# motherboard_rev1.net
KiCad netlist of a schematic drawn in EAGLE
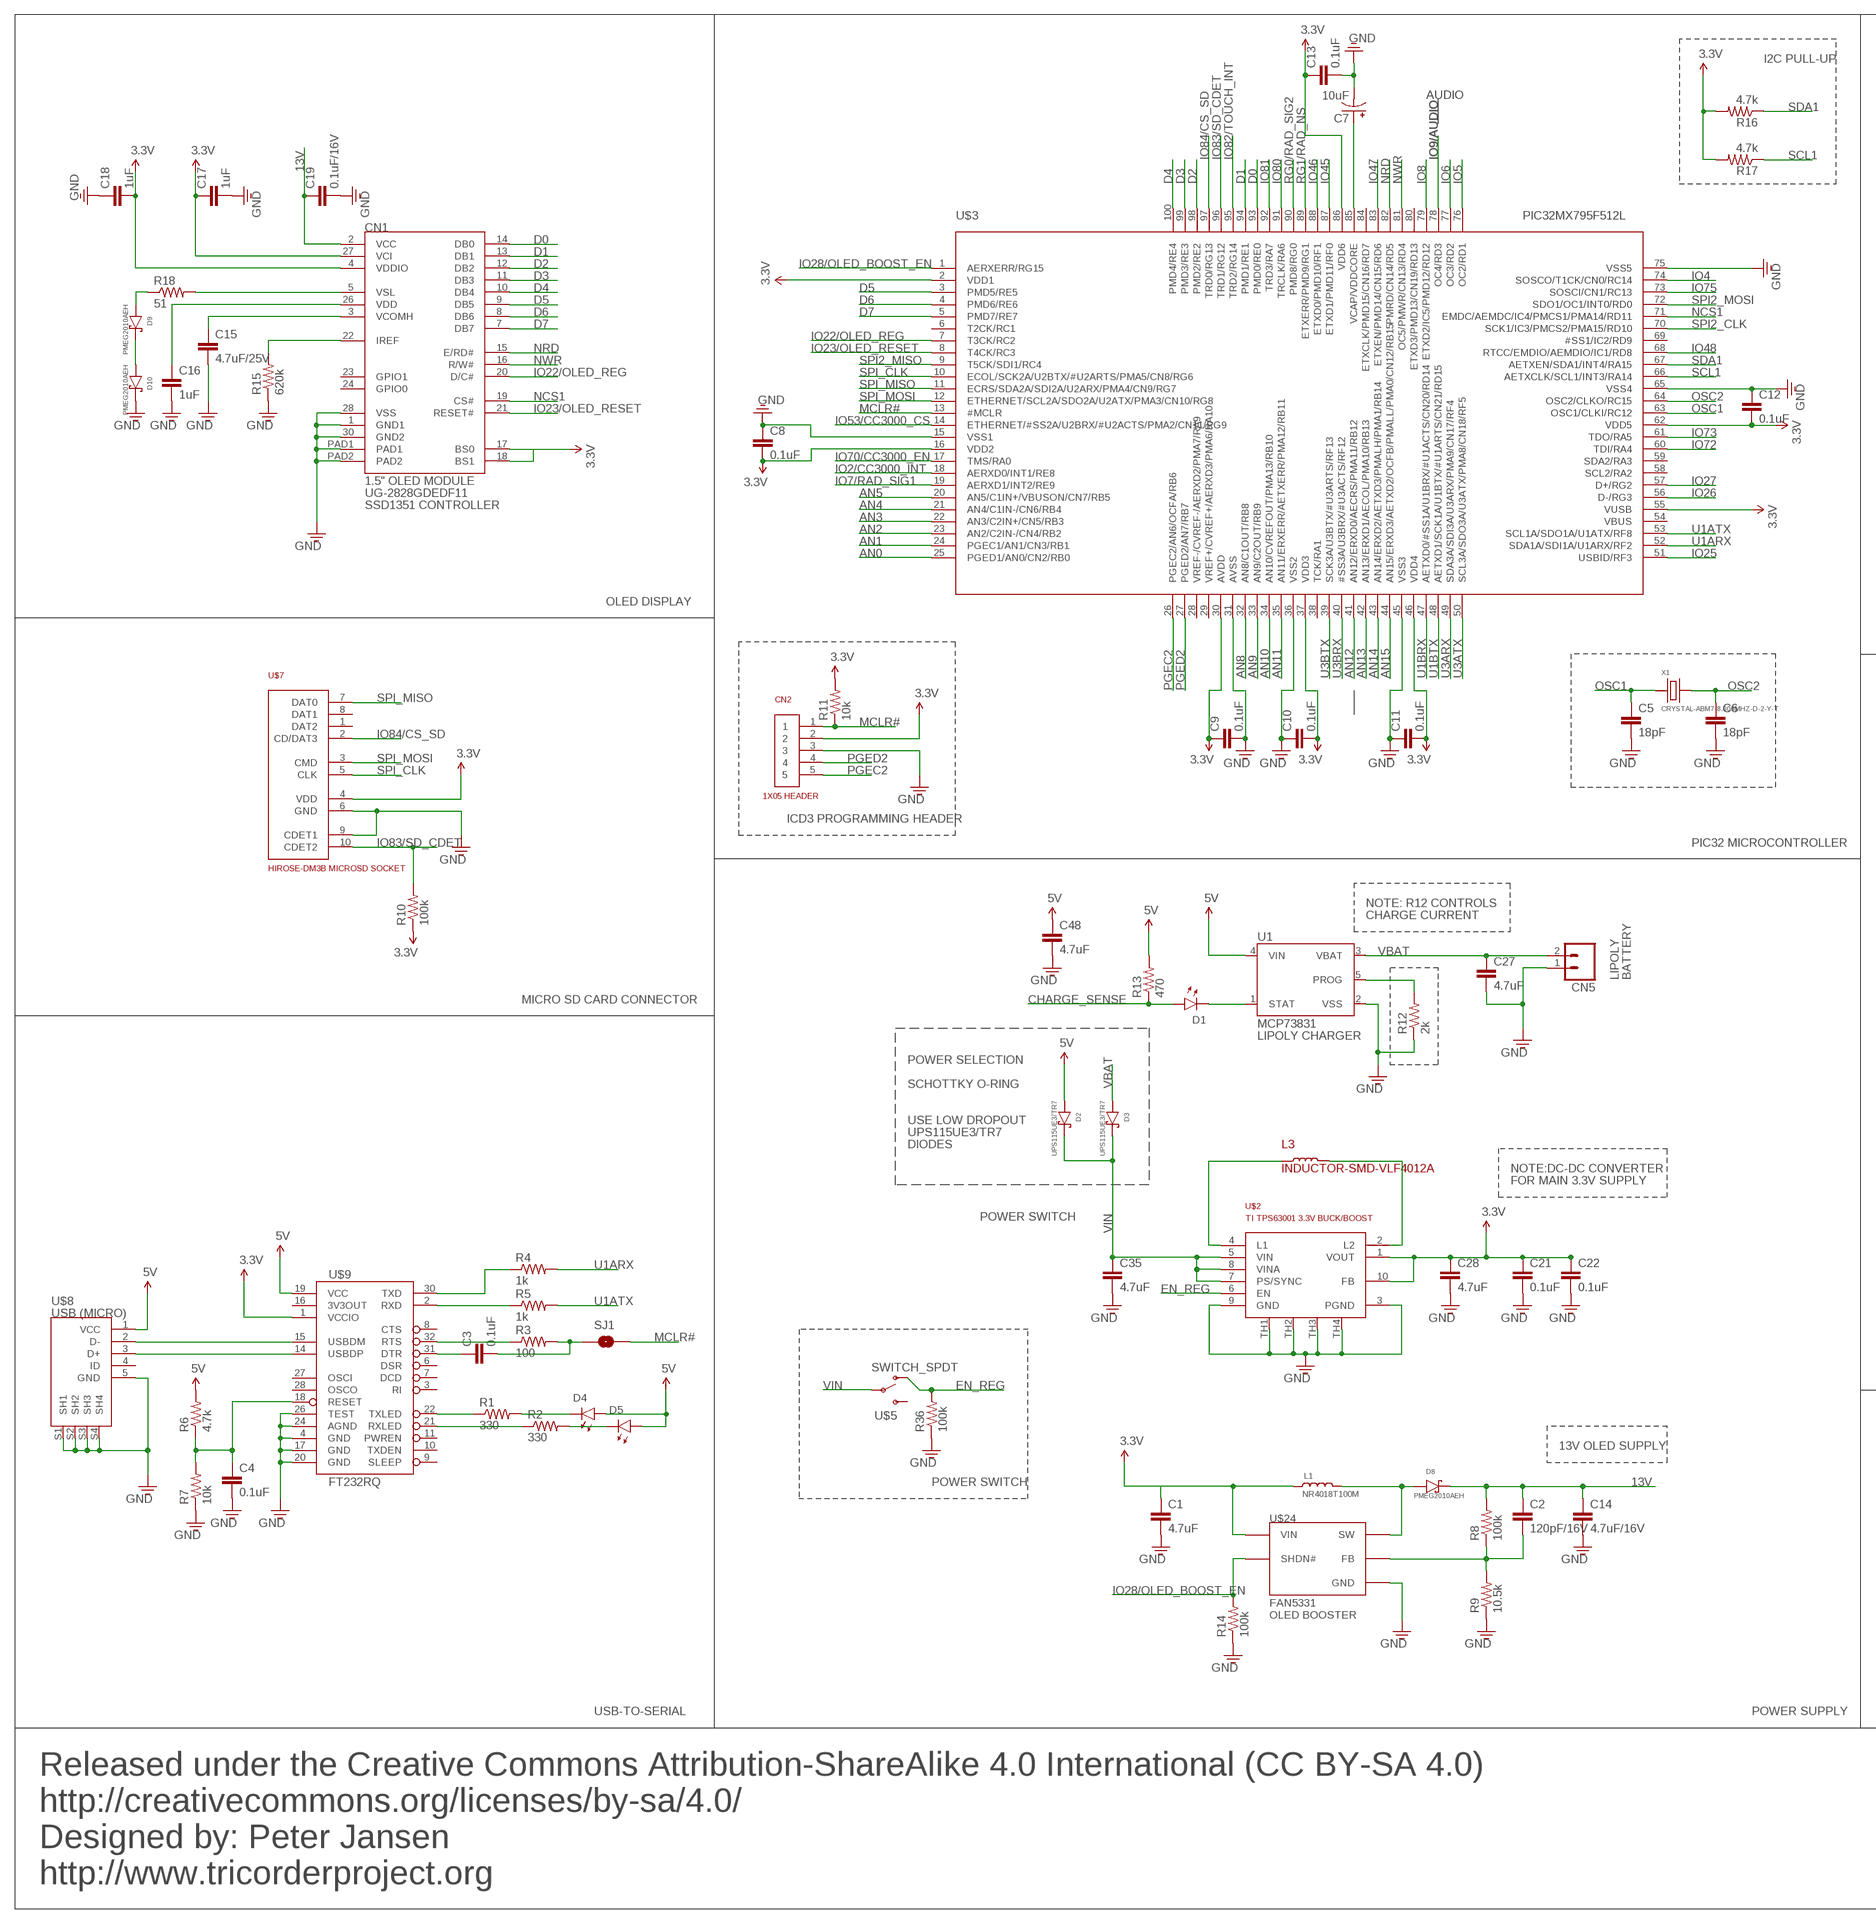
[diagram p0: schematic, sheet 1, part 1 of 2]
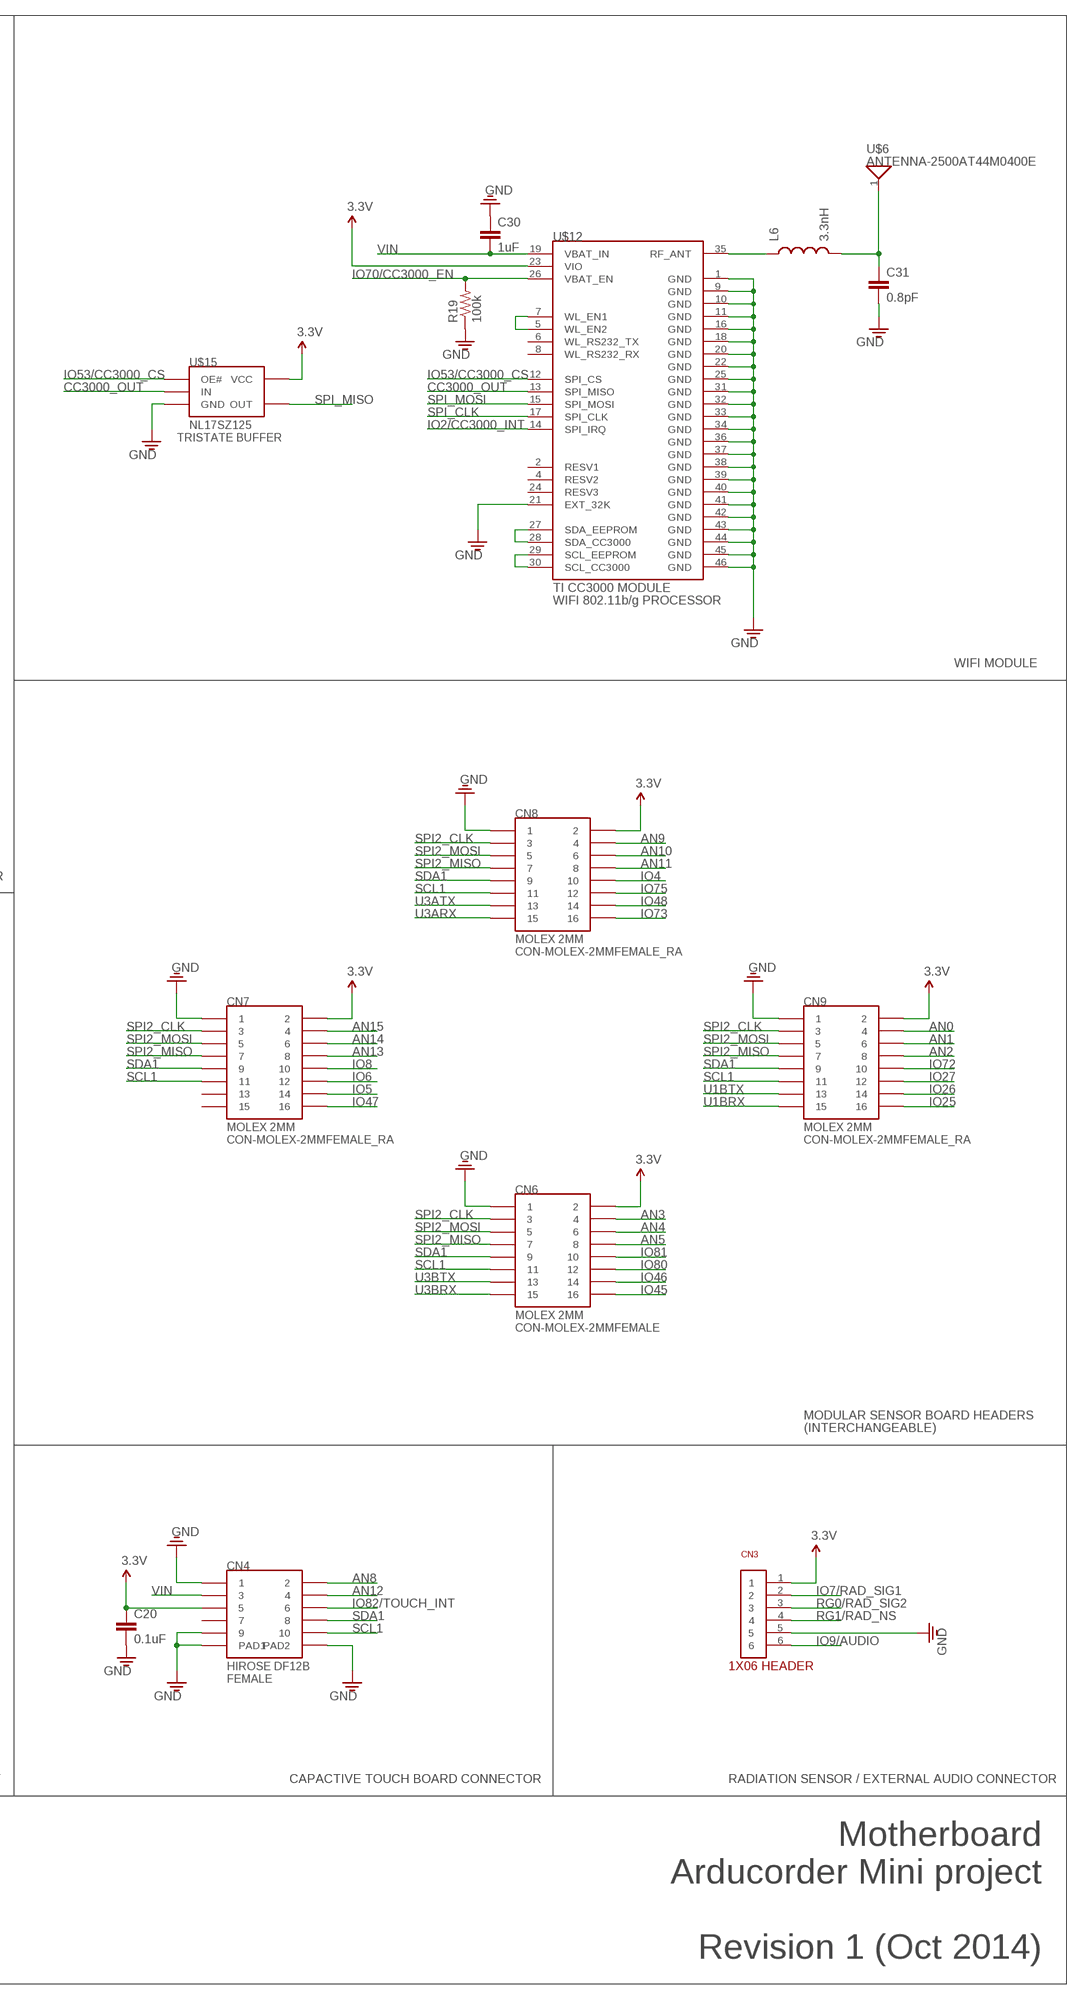
[diagram p1: schematic, sheet 1, part 2 of 2]

(export (version "E")
  (design (tool "Eeschema 10.0.6"))
  (components
    (comp (ref "C1")
      (value "4.7uF")
      (footprint "eagle-import:0603")
      (libsource (lib "eagle-import") (part "CAP0603"))
    )
    (comp (ref "C2")
      (value "120pF/16V")
      (footprint "eagle-import:0603")
      (libsource (lib "eagle-import") (part "notes_mark5a1_CAP0603"))
    )
    (comp (ref "C3")
      (value "0.1uF")
      (footprint "eagle-import:0603")
      (libsource (lib "eagle-import") (part "CAP0603"))
    )
    (comp (ref "C4")
      (value "0.1uF")
      (footprint "eagle-import:0603")
      (libsource (lib "eagle-import") (part "CAP0603"))
    )
    (comp (ref "C5")
      (value "18pF")
      (footprint "eagle-import:0603")
      (libsource (lib "eagle-import") (part "CAP0603"))
    )
    (comp (ref "C6")
      (value "18pF")
      (footprint "eagle-import:0603")
      (libsource (lib "eagle-import") (part "CAP0603"))
    )
    (comp (ref "C7")
      (value "10uF")
      (footprint "eagle-import:EIA3216")
      (libsource (lib "eagle-import") (part "CAP_POL1206"))
    )
    (comp (ref "C8")
      (value "0.1uF")
      (footprint "eagle-import:0603")
      (libsource (lib "eagle-import") (part "CAP0603"))
    )
    (comp (ref "C9")
      (value "0.1uF")
      (footprint "eagle-import:0603")
      (libsource (lib "eagle-import") (part "CAP0603"))
    )
    (comp (ref "C10")
      (value "0.1uF")
      (footprint "eagle-import:0603")
      (libsource (lib "eagle-import") (part "CAP0603"))
    )
    (comp (ref "C11")
      (value "0.1uF")
      (footprint "eagle-import:0603")
      (libsource (lib "eagle-import") (part "CAP0603"))
    )
    (comp (ref "C12")
      (value "0.1uF")
      (footprint "eagle-import:0603")
      (libsource (lib "eagle-import") (part "CAP0603"))
    )
    (comp (ref "C13")
      (value "0.1uF")
      (footprint "eagle-import:0603")
      (libsource (lib "eagle-import") (part "CAP0603"))
    )
    (comp (ref "C14")
      (value "4.7uF/16V")
      (footprint "eagle-import:0603")
      (libsource (lib "eagle-import") (part "CAP0603"))
    )
    (comp (ref "C15")
      (value "4.7uF/25V")
      (footprint "eagle-import:0603")
      (libsource (lib "eagle-import") (part "CAP0603"))
    )
    (comp (ref "C16")
      (value "1uF")
      (footprint "eagle-import:0603")
      (libsource (lib "eagle-import") (part "CAP0603"))
    )
    (comp (ref "C17")
      (value "1uF")
      (footprint "eagle-import:0603")
      (libsource (lib "eagle-import") (part "CAP0603"))
    )
    (comp (ref "C18")
      (value "1uF")
      (footprint "eagle-import:0603")
      (libsource (lib "eagle-import") (part "CAP0603"))
    )
    (comp (ref "C19")
      (value "0.1uF/16V")
      (footprint "eagle-import:0603")
      (libsource (lib "eagle-import") (part "CAP0603"))
    )
    (comp (ref "C20")
      (value "0.1uF")
      (footprint "eagle-import:0603")
      (libsource (lib "eagle-import") (part "CAP0603"))
    )
    (comp (ref "C21")
      (value "0.1uF")
      (footprint "eagle-import:0603")
      (libsource (lib "eagle-import") (part "CAP0603"))
    )
    (comp (ref "C22")
      (value "0.1uF")
      (footprint "eagle-import:0603")
      (libsource (lib "eagle-import") (part "CAP0603"))
    )
    (comp (ref "C27")
      (value "4.7uF")
      (footprint "eagle-import:0603")
      (libsource (lib "eagle-import") (part "CAP0603"))
    )
    (comp (ref "C28")
      (value "4.7uF")
      (footprint "eagle-import:0603")
      (libsource (lib "eagle-import") (part "CAP0603"))
    )
    (comp (ref "C30")
      (value "1uF")
      (footprint "eagle-import:0603")
      (libsource (lib "eagle-import") (part "CAP0603"))
    )
    (comp (ref "C31")
      (value "0.8pF")
      (footprint "eagle-import:C0402")
      (libsource (lib "eagle-import") (part "CAP0402"))
    )
    (comp (ref "C35")
      (value "4.7uF")
      (footprint "eagle-import:0603")
      (libsource (lib "eagle-import") (part "CAP0603"))
    )
    (comp (ref "C48")
      (value "4.7uF")
      (footprint "eagle-import:0603")
      (libsource (lib "eagle-import") (part "CAP0603"))
    )
    (comp (ref "CN1")
      (value "UG-2828GDEDF11-1.5OLED")
      (footprint "eagle-import:XF2M-3015-1A-1.5LCD")
      (libsource (lib "eagle-import") (part "UG-2828GDEDF11-1.5OLED"))
    )
    (comp (ref "CN2")
      (value "1X05")
      (footprint "eagle-import:1X05")
      (libsource (lib "eagle-import") (part "1X05"))
    )
    (comp (ref "CN3")
      (value "PHF-106-01-L-S")
      (footprint "eagle-import:1X06")
      (libsource (lib "eagle-import") (part "1X06"))
    )
    (comp (ref "CN4")
      (value "FEMALE")
      (footprint "eagle-import:DF12B(3.0)-10DP-0.5V(86)")
      (libsource (lib "eagle-import") (part "CON-HIROSE-DF12FEMALE"))
    )
    (comp (ref "CN5")
      (value "M02-JST-2MM-SMT")
      (footprint "eagle-import:JST-2-SMD")
      (libsource (lib "eagle-import") (part "M02-JST-2MM-SMT"))
    )
    (comp (ref "CN6")
      (value "CON-MOLEX-2MMFEMALE")
      (footprint "eagle-import:MOLEX-0791091007")
      (libsource (lib "eagle-import") (part "CON-MOLEX-2MMFEMALE"))
    )
    (comp (ref "CN7")
      (value "CON-MOLEX-2MMFEMALE_RA")
      (footprint "eagle-import:MOLEX-87368-1624")
      (libsource (lib "eagle-import") (part "CON-MOLEX-2MMFEMALE_RA"))
    )
    (comp (ref "CN8")
      (value "CON-MOLEX-2MMFEMALE_RA")
      (footprint "eagle-import:MOLEX-87368-1624")
      (libsource (lib "eagle-import") (part "CON-MOLEX-2MMFEMALE_RA"))
    )
    (comp (ref "CN9")
      (value "CON-MOLEX-2MMFEMALE_RA")
      (footprint "eagle-import:MOLEX-87368-1624")
      (libsource (lib "eagle-import") (part "CON-MOLEX-2MMFEMALE_RA"))
    )
    (comp (ref "D1")
      (value "0605-LED")
      (footprint "eagle-import:0603-LED")
      (libsource (lib "eagle-import") (part "0605-LED"))
    )
    (comp (ref "D2")
      (value "UPS115UE3/TR7")
      (footprint "eagle-import:DO-214BA")
      (libsource (lib "eagle-import") (part "DIODE-SCHOTTKY"))
    )
    (comp (ref "D3")
      (value "UPS115UE3/TR7")
      (footprint "eagle-import:DO-214BA")
      (libsource (lib "eagle-import") (part "DIODE-SCHOTTKY"))
    )
    (comp (ref "D4")
      (value "0605-LED")
      (footprint "eagle-import:0603-LED")
      (libsource (lib "eagle-import") (part "0605-LED"))
    )
    (comp (ref "D5")
      (value "0605-LED")
      (footprint "eagle-import:0603-LED")
      (libsource (lib "eagle-import") (part "0605-LED"))
    )
    (comp (ref "D8")
      (value "PMEG2010AEH")
      (footprint "eagle-import:SOD123F")
      (libsource (lib "eagle-import") (part "DIODE-SCHOTTKYSOD123F"))
    )
    (comp (ref "D9")
      (value "PMEG2010AEH")
      (footprint "eagle-import:SOD123F")
      (libsource (lib "eagle-import") (part "DIODE-SCHOTTKYSOD123F"))
    )
    (comp (ref "D10")
      (value "PMEG2010AEH")
      (footprint "eagle-import:SOD123F")
      (libsource (lib "eagle-import") (part "DIODE-SCHOTTKYSOD123F"))
    )
    (comp (ref "L1")
      (value "NR4018T100M")
      (footprint "eagle-import:NR4018T100M")
      (libsource (lib "eagle-import") (part "INDUCTORNR4018T100M"))
    )
    (comp (ref "L3")
      (value "INDUCTOR-SMD-VLF4012A")
      (footprint "eagle-import:VLF4012A")
      (libsource (lib "eagle-import") (part "INDUCTOR-SMD-VLF4012A"))
    )
    (comp (ref "L6")
      (value "3.3nH")
      (footprint "eagle-import:C0402")
      (libsource (lib "eagle-import") (part "INDUCTOR0402"))
    )
    (comp (ref "R1")
      (value "330")
      (footprint "eagle-import:0603")
      (libsource (lib "eagle-import") (part "RESISTOR0603"))
    )
    (comp (ref "R2")
      (value "330")
      (footprint "eagle-import:0603")
      (libsource (lib "eagle-import") (part "RESISTOR0603"))
    )
    (comp (ref "R3")
      (value "100")
      (footprint "eagle-import:0603")
      (libsource (lib "eagle-import") (part "RESISTOR0603"))
    )
    (comp (ref "R4")
      (value "1k")
      (footprint "eagle-import:0603")
      (libsource (lib "eagle-import") (part "RESISTOR0603"))
    )
    (comp (ref "R5")
      (value "1k")
      (footprint "eagle-import:0603")
      (libsource (lib "eagle-import") (part "RESISTOR0603"))
    )
    (comp (ref "R6")
      (value "4.7k")
      (footprint "eagle-import:0603")
      (libsource (lib "eagle-import") (part "RESISTOR0603"))
    )
    (comp (ref "R7")
      (value "10k")
      (footprint "eagle-import:0603")
      (libsource (lib "eagle-import") (part "RESISTOR0603"))
    )
    (comp (ref "R8")
      (value "100k")
      (footprint "eagle-import:0603")
      (libsource (lib "eagle-import") (part "notes_mark5a1_RESISTOR0603"))
    )
    (comp (ref "R9")
      (value "10.5k")
      (footprint "eagle-import:0603")
      (libsource (lib "eagle-import") (part "notes_mark5a1_RESISTOR0603"))
    )
    (comp (ref "R10")
      (value "100k")
      (footprint "eagle-import:0603")
      (libsource (lib "eagle-import") (part "RESISTOR0603"))
    )
    (comp (ref "R11")
      (value "10k")
      (footprint "eagle-import:0603")
      (libsource (lib "eagle-import") (part "RESISTOR0603"))
    )
    (comp (ref "R12")
      (value "2k")
      (footprint "eagle-import:0603")
      (libsource (lib "eagle-import") (part "RESISTOR0603"))
    )
    (comp (ref "R13")
      (value "470")
      (footprint "eagle-import:0603")
      (libsource (lib "eagle-import") (part "RESISTOR0603"))
    )
    (comp (ref "R14")
      (value "100k")
      (footprint "eagle-import:0603")
      (libsource (lib "eagle-import") (part "notes_mark5a1_RESISTOR0603"))
    )
    (comp (ref "R15")
      (value "620k")
      (footprint "eagle-import:0603")
      (libsource (lib "eagle-import") (part "notes_mark5a1_RESISTOR0603"))
    )
    (comp (ref "R16")
      (value "4.7k")
      (footprint "eagle-import:0603")
      (libsource (lib "eagle-import") (part "RESISTOR0603"))
    )
    (comp (ref "R17")
      (value "4.7k")
      (footprint "eagle-import:0603")
      (libsource (lib "eagle-import") (part "RESISTOR0603"))
    )
    (comp (ref "R18")
      (value "51")
      (footprint "eagle-import:0603")
      (libsource (lib "eagle-import") (part "notes_mark5a1_RESISTOR0603"))
    )
    (comp (ref "R19")
      (value "100k")
      (footprint "eagle-import:0603")
      (libsource (lib "eagle-import") (part "notes_mark5a1_RESISTOR0603"))
    )
    (comp (ref "R36")
      (value "100k")
      (footprint "eagle-import:0603")
      (libsource (lib "eagle-import") (part "RESISTOR0603"))
    )
    (comp (ref "SJ1")
      (value "SOLDERJUMPERTRACE")
      (footprint "eagle-import:SJ_2S-TRACE")
      (libsource (lib "eagle-import") (part "SOLDERJUMPERTRACE"))
    )
    (comp (ref "U$2")
      (value "TI-TPS63001-3.3V-BUCKBOOST")
      (footprint "eagle-import:TPS63001")
      (libsource (lib "eagle-import") (part "TI-TPS63001-3.3V-BUCKBOOST"))
    )
    (comp (ref "U$3")
      (value "PIC32MX795F512L-80I/PF")
      (footprint "eagle-import:SQFP-S-14X14-100")
      (libsource (lib "eagle-import") (part "PIC32MX795F512L-80I/PF"))
    )
    (comp (ref "U$5")
      (value "SWITCH_SPDT")
      (footprint "eagle-import:KPS-1290")
      (libsource (lib "eagle-import") (part "SWITCH_SPDT"))
    )
    (comp (ref "U$6")
      (value "ANTENNA-2500AT44M0400E")
      (footprint "eagle-import:ANT-2500AT44M0400E")
      (libsource (lib "eagle-import") (part "ANTENNA-2500AT44M0400E"))
    )
    (comp (ref "U$7")
      (value "CON-HIROSE-DM3B-MICROSD")
      (footprint "eagle-import:CON-HIROSE-DM3B-MICROSD")
      (libsource (lib "eagle-import") (part "CON-HIROSE-DM3B-MICROSD"))
    )
    (comp (ref "U$8")
      (value "USB-MICROB")
      (footprint "eagle-import:FCI-10104110-0001LF")
      (libsource (lib "eagle-import") (part "USB-MICROB"))
    )
    (comp (ref "U$9")
      (value "FT232RQ")
      (footprint "eagle-import:QFN-32")
      (libsource (lib "eagle-import") (part "FT232RQ"))
    )
    (comp (ref "U$12")
      (value "CC3000")
      (footprint "eagle-import:CC3000")
      (libsource (lib "eagle-import") (part "CC3000"))
    )
    (comp (ref "U$15")
      (value "BUFFER-NL17SZ125")
      (footprint "eagle-import:TSOP-5")
      (libsource (lib "eagle-import") (part "BUFFER-NL17SZ125"))
    )
    (comp (ref "U$24")
      (value "FAN5331-BOOST")
      (footprint "eagle-import:TSOP-5")
      (libsource (lib "eagle-import") (part "FAN5331-BOOST"))
    )
    (comp (ref "U1")
      (value "MCP73831")
      (footprint "eagle-import:SOT23-5")
      (libsource (lib "eagle-import") (part "MCP73831"))
    )
    (comp (ref "X1")
      (value "CRYSTAL-ABM7-8.000MHZ-D-2-Y-T")
      (footprint "eagle-import:CYRSTAL-6.0X3.5MM")
      (libsource (lib "eagle-import") (part "CRYSTAL-ABM7-8.000MHZ-D-2-Y-T"))
    )
  )
  (nets
    (net (code "1") (name "/13V") (class "Default")
      (node (ref "C14") (pin "1") (pinfunction "1_1") (pintype "passive"))
      (node (ref "C19") (pin "1") (pinfunction "1_1") (pintype "passive"))
      (node (ref "C2") (pin "1") (pinfunction "1_1") (pintype "passive"))
      (node (ref "CN1") (pin "2") (pinfunction "VCC_2") (pintype "bidirectional"))
      (node (ref "D8") (pin "1") (pinfunction "CATHODE_1") (pintype "bidirectional"))
      (node (ref "R8") (pin "2") (pinfunction "2_2") (pintype "passive"))
    )
    (net (code "2") (name "/AN0") (class "Default")
      (node (ref "CN9") (pin "4") (pinfunction "4_4") (pintype "bidirectional"))
      (node (ref "U$3") (pin "25") (pinfunction "PGED1/AN0/CN2/RB0_25") (pintype "bidirectional"))
    )
    (net (code "3") (name "/AN1") (class "Default")
      (node (ref "CN9") (pin "6") (pinfunction "6_6") (pintype "bidirectional"))
      (node (ref "U$3") (pin "24") (pinfunction "PGEC1/AN1/CN3/RB1_24") (pintype "bidirectional"))
    )
    (net (code "4") (name "/AN2") (class "Default")
      (node (ref "CN9") (pin "8") (pinfunction "8_8") (pintype "bidirectional"))
      (node (ref "U$3") (pin "23") (pinfunction "AN2/C2IN-/CN4/RB2_23") (pintype "bidirectional"))
    )
    (net (code "5") (name "/AN3") (class "Default")
      (node (ref "CN6") (pin "4") (pinfunction "4_4") (pintype "bidirectional"))
      (node (ref "U$3") (pin "22") (pinfunction "AN3/C2IN+/CN5/RB3_22") (pintype "bidirectional"))
    )
    (net (code "6") (name "/AN4") (class "Default")
      (node (ref "CN6") (pin "6") (pinfunction "6_6") (pintype "bidirectional"))
      (node (ref "U$3") (pin "21") (pinfunction "AN4/C1IN-/CN6/RB4_21") (pintype "bidirectional"))
    )
    (net (code "7") (name "/AN5") (class "Default")
      (node (ref "CN6") (pin "8") (pinfunction "8_8") (pintype "bidirectional"))
      (node (ref "U$3") (pin "20") (pinfunction "AN5/C1IN+/VBUSON/CN7/RB5_20") (pintype "bidirectional"))
    )
    (net (code "8") (name "/AN8") (class "Default")
      (node (ref "CN4") (pin "2") (pinfunction "2_2") (pintype "bidirectional"))
      (node (ref "U$3") (pin "32") (pinfunction "AN8/C1OUT/RB8_32") (pintype "bidirectional"))
    )
    (net (code "9") (name "/AN9") (class "Default")
      (node (ref "CN8") (pin "4") (pinfunction "4_4") (pintype "bidirectional"))
      (node (ref "U$3") (pin "33") (pinfunction "AN9/C2OUT/RB9_33") (pintype "bidirectional"))
    )
    (net (code "10") (name "/AN10") (class "Default")
      (node (ref "CN8") (pin "6") (pinfunction "6_6") (pintype "bidirectional"))
      (node (ref "U$3") (pin "34") (pinfunction "AN10/CVREFOUT/PMA13/RB10_34") (pintype "bidirectional"))
    )
    (net (code "11") (name "/AN11") (class "Default")
      (node (ref "CN8") (pin "8") (pinfunction "8_8") (pintype "bidirectional"))
      (node (ref "U$3") (pin "35") (pinfunction "AN11/ERXERR/AETXERR/PMA12/RB11_35") (pintype "bidirectional"))
    )
    (net (code "12") (name "/AN12") (class "Default")
      (node (ref "CN4") (pin "4") (pinfunction "4_4") (pintype "bidirectional"))
      (node (ref "U$3") (pin "41") (pinfunction "AN12/ERXD0/AECRS/PMA11/RB12_41") (pintype "bidirectional"))
    )
    (net (code "13") (name "/AN13") (class "Default")
      (node (ref "CN7") (pin "8") (pinfunction "8_8") (pintype "bidirectional"))
      (node (ref "U$3") (pin "42") (pinfunction "AN13/ERXD1/AECOL/PMA10/RB13_42") (pintype "bidirectional"))
    )
    (net (code "14") (name "/AN14") (class "Default")
      (node (ref "CN7") (pin "6") (pinfunction "6_6") (pintype "bidirectional"))
      (node (ref "U$3") (pin "43") (pinfunction "AN14/ERXD2/AETXD3/PMALH/PMA1/RB14_43") (pintype "bidirectional"))
    )
    (net (code "15") (name "/AN15") (class "Default")
      (node (ref "CN7") (pin "4") (pinfunction "4_4") (pintype "bidirectional"))
      (node (ref "U$3") (pin "44") (pinfunction "AN15/ERXD3/AETXD2/OCFB/PMALL/PMA0/CN12/RB15_44") (pintype "bidirectional"))
    )
    (net (code "16") (name "/CC3000_OUT") (class "Default")
      (node (ref "U$12") (pin "13") (pinfunction "SPI_MISO_13") (pintype "bidirectional"))
      (node (ref "U$15") (pin "2") (pinfunction "IN_2") (pintype "bidirectional"))
    )
    (net (code "17") (name "/CHARGE_SENSE") (class "Default")
      (node (ref "D1") (pin "ANODE") (pinfunction "ANODE_ANODE") (pintype "bidirectional"))
      (node (ref "R13") (pin "1") (pinfunction "1_1") (pintype "passive"))
    )
    (net (code "18") (name "/D0") (class "Default")
      (node (ref "CN1") (pin "14") (pinfunction "DB0_14") (pintype "bidirectional"))
      (node (ref "U$3") (pin "93") (pinfunction "PMD0/RE0_93") (pintype "bidirectional"))
    )
    (net (code "19") (name "/D1") (class "Default")
      (node (ref "CN1") (pin "13") (pinfunction "DB1_13") (pintype "bidirectional"))
      (node (ref "U$3") (pin "94") (pinfunction "PMD1/RE1_94") (pintype "bidirectional"))
    )
    (net (code "20") (name "/D2") (class "Default")
      (node (ref "CN1") (pin "12") (pinfunction "DB2_12") (pintype "bidirectional"))
      (node (ref "U$3") (pin "98") (pinfunction "PMD2/RE2_98") (pintype "bidirectional"))
    )
    (net (code "21") (name "/D3") (class "Default")
      (node (ref "CN1") (pin "11") (pinfunction "DB3_11") (pintype "bidirectional"))
      (node (ref "U$3") (pin "99") (pinfunction "PMD3/RE3_99") (pintype "bidirectional"))
    )
    (net (code "22") (name "/D4") (class "Default")
      (node (ref "CN1") (pin "10") (pinfunction "DB4_10") (pintype "bidirectional"))
      (node (ref "U$3") (pin "100") (pinfunction "PMD4/RE4_100") (pintype "bidirectional"))
    )
    (net (code "23") (name "/D5") (class "Default")
      (node (ref "CN1") (pin "9") (pinfunction "DB5_9") (pintype "bidirectional"))
      (node (ref "U$3") (pin "3") (pinfunction "PMD5/RE5_3") (pintype "bidirectional"))
    )
    (net (code "24") (name "/D6") (class "Default")
      (node (ref "CN1") (pin "8") (pinfunction "DB6_8") (pintype "bidirectional"))
      (node (ref "U$3") (pin "4") (pinfunction "PMD6/RE6_4") (pintype "bidirectional"))
    )
    (net (code "25") (name "/D7") (class "Default")
      (node (ref "CN1") (pin "7") (pinfunction "DB7_7") (pintype "bidirectional"))
      (node (ref "U$3") (pin "5") (pinfunction "PMD7/RE7_5") (pintype "bidirectional"))
    )
    (net (code "26") (name "/EN_REG") (class "Default")
      (node (ref "R36") (pin "2") (pinfunction "2_2") (pintype "passive"))
      (node (ref "U$2") (pin "6") (pinfunction "EN_6") (pintype "bidirectional"))
      (node (ref "U$5") (pin "O") (pinfunction "O_O") (pintype "passive"))
    )
    (net (code "27") (name "/IO2{slash}CC3000_INT") (class "Default")
      (node (ref "U$12") (pin "14") (pinfunction "SPI_IRQ_14") (pintype "bidirectional"))
      (node (ref "U$3") (pin "18") (pinfunction "AERXD0/INT1/RE8_18") (pintype "bidirectional"))
    )
    (net (code "28") (name "/IO4") (class "Default")
      (node (ref "CN8") (pin "10") (pinfunction "10_10") (pintype "bidirectional"))
      (node (ref "U$3") (pin "74") (pinfunction "SOSCO/T1CK/CN0/RC14_74") (pintype "bidirectional"))
    )
    (net (code "29") (name "/IO5") (class "Default")
      (node (ref "CN7") (pin "14") (pinfunction "14_14") (pintype "bidirectional"))
      (node (ref "U$3") (pin "76") (pinfunction "OC2/RD1_76") (pintype "bidirectional"))
    )
    (net (code "30") (name "/IO6") (class "Default")
      (node (ref "CN7") (pin "12") (pinfunction "12_12") (pintype "bidirectional"))
      (node (ref "U$3") (pin "77") (pinfunction "OC3/RD2_77") (pintype "bidirectional"))
    )
    (net (code "31") (name "/IO7{slash}RAD_SIG1") (class "Default")
      (node (ref "CN3") (pin "2") (pinfunction "2_2") (pintype "bidirectional"))
      (node (ref "U$3") (pin "19") (pinfunction "AERXD1/INT2/RE9_19") (pintype "bidirectional"))
    )
    (net (code "32") (name "/IO8") (class "Default")
      (node (ref "CN7") (pin "10") (pinfunction "10_10") (pintype "bidirectional"))
      (node (ref "U$3") (pin "79") (pinfunction "ETXD2/IC5/PMD12/RD12_79") (pintype "bidirectional"))
    )
    (net (code "33") (name "/IO9{slash}AUDIO") (class "Default")
      (node (ref "CN3") (pin "6") (pinfunction "6_6") (pintype "bidirectional"))
      (node (ref "U$3") (pin "78") (pinfunction "OC4/RD3_78") (pintype "bidirectional"))
    )
    (net (code "34") (name "/IO22{slash}OLED_REG") (class "Default")
      (node (ref "CN1") (pin "20") (pinfunction "D/C#_20") (pintype "bidirectional"))
      (node (ref "U$3") (pin "7") (pinfunction "T3CK/RC2_7") (pintype "bidirectional"))
    )
    (net (code "35") (name "/IO23{slash}OLED_RESET") (class "Default")
      (node (ref "CN1") (pin "21") (pinfunction "RESET#_21") (pintype "bidirectional"))
      (node (ref "U$3") (pin "8") (pinfunction "T4CK/RC3_8") (pintype "bidirectional"))
    )
    (net (code "36") (name "/IO25") (class "Default")
      (node (ref "CN9") (pin "16") (pinfunction "16_16") (pintype "bidirectional"))
      (node (ref "U$3") (pin "51") (pinfunction "USBID/RF3_51") (pintype "bidirectional"))
    )
    (net (code "37") (name "/IO26") (class "Default")
      (node (ref "CN9") (pin "14") (pinfunction "14_14") (pintype "bidirectional"))
      (node (ref "U$3") (pin "56") (pinfunction "D-/RG3_56") (pintype "bidirectional"))
    )
    (net (code "38") (name "/IO27") (class "Default")
      (node (ref "CN9") (pin "12") (pinfunction "12_12") (pintype "bidirectional"))
      (node (ref "U$3") (pin "57") (pinfunction "D+/RG2_57") (pintype "bidirectional"))
    )
    (net (code "39") (name "/IO28{slash}OLED_BOOST_EN") (class "Default")
      (node (ref "R14") (pin "2") (pinfunction "2_2") (pintype "passive"))
      (node (ref "U$24") (pin "4") (pinfunction "SHDN#_4") (pintype "bidirectional"))
      (node (ref "U$3") (pin "1") (pinfunction "AERXERR/RG15_1") (pintype "bidirectional"))
    )
    (net (code "40") (name "/IO45") (class "Default")
      (node (ref "CN6") (pin "16") (pinfunction "16_16") (pintype "bidirectional"))
      (node (ref "U$3") (pin "87") (pinfunction "ETXD1/PMD11/RF0_87") (pintype "bidirectional"))
    )
    (net (code "41") (name "/IO46") (class "Default")
      (node (ref "CN6") (pin "14") (pinfunction "14_14") (pintype "bidirectional"))
      (node (ref "U$3") (pin "88") (pinfunction "ETXD0/PMD10/RF1_88") (pintype "bidirectional"))
    )
    (net (code "42") (name "/IO47") (class "Default")
      (node (ref "CN7") (pin "16") (pinfunction "16_16") (pintype "bidirectional"))
      (node (ref "U$3") (pin "83") (pinfunction "ETXEN/PMD14/CN15/RD6_83") (pintype "bidirectional"))
    )
    (net (code "43") (name "/IO48") (class "Default")
      (node (ref "CN8") (pin "14") (pinfunction "14_14") (pintype "bidirectional"))
      (node (ref "U$3") (pin "68") (pinfunction "RTCC/EMDIO/AEMDIO/IC1/RD8_68") (pintype "bidirectional"))
    )
    (net (code "44") (name "/IO53{slash}CC3000_CS") (class "Default")
      (node (ref "U$12") (pin "12") (pinfunction "SPI_CS_12") (pintype "bidirectional"))
      (node (ref "U$15") (pin "1") (pinfunction "OE#_1") (pintype "bidirectional"))
      (node (ref "U$3") (pin "14") (pinfunction "ETHERNET/#SS2A/U2BRX/#U2ACTS/PMA2/CN11/RG9_14") (pintype "bidirectional"))
    )
    (net (code "45") (name "/IO70{slash}CC3000_EN") (class "Default")
      (node (ref "R19") (pin "2") (pinfunction "2_2") (pintype "passive"))
      (node (ref "U$12") (pin "26") (pinfunction "VBAT_EN_26") (pintype "bidirectional"))
      (node (ref "U$3") (pin "17") (pinfunction "TMS/RA0_17") (pintype "bidirectional"))
    )
    (net (code "46") (name "/IO72") (class "Default")
      (node (ref "CN9") (pin "10") (pinfunction "10_10") (pintype "bidirectional"))
      (node (ref "U$3") (pin "60") (pinfunction "TDI/RA4_60") (pintype "bidirectional"))
    )
    (net (code "47") (name "/IO73") (class "Default")
      (node (ref "CN8") (pin "16") (pinfunction "16_16") (pintype "bidirectional"))
      (node (ref "U$3") (pin "61") (pinfunction "TDO/RA5_61") (pintype "bidirectional"))
    )
    (net (code "48") (name "/IO75") (class "Default")
      (node (ref "CN8") (pin "12") (pinfunction "12_12") (pintype "bidirectional"))
      (node (ref "U$3") (pin "73") (pinfunction "SOSCI/CN1/RC13_73") (pintype "bidirectional"))
    )
    (net (code "49") (name "/IO80") (class "Default")
      (node (ref "CN6") (pin "12") (pinfunction "12_12") (pintype "bidirectional"))
      (node (ref "U$3") (pin "91") (pinfunction "TRCLK/RA6_91") (pintype "bidirectional"))
    )
    (net (code "50") (name "/IO81") (class "Default")
      (node (ref "CN6") (pin "10") (pinfunction "10_10") (pintype "bidirectional"))
      (node (ref "U$3") (pin "92") (pinfunction "TRD3/RA7_92") (pintype "bidirectional"))
    )
    (net (code "51") (name "/IO82{slash}TOUCH_INT") (class "Default")
      (node (ref "CN4") (pin "6") (pinfunction "6_6") (pintype "bidirectional"))
      (node (ref "U$3") (pin "95") (pinfunction "TRD2/RG14_95") (pintype "bidirectional"))
    )
    (net (code "52") (name "/IO83{slash}SD_CDET") (class "Default")
      (node (ref "R10") (pin "2") (pinfunction "2_2") (pintype "passive"))
      (node (ref "U$3") (pin "96") (pinfunction "TRD1/RG12_96") (pintype "bidirectional"))
      (node (ref "U$7") (pin "10") (pinfunction "CDET2_10") (pintype "bidirectional"))
    )
    (net (code "53") (name "/IO84{slash}CS_SD") (class "Default")
      (node (ref "U$3") (pin "97") (pinfunction "TRD0/RG13_97") (pintype "bidirectional"))
      (node (ref "U$7") (pin "2") (pinfunction "CD/DAT3_2") (pintype "bidirectional"))
    )
    (net (code "54") (name "/MCLR#") (class "Default")
      (node (ref "CN2") (pin "1") (pinfunction "1_1") (pintype "bidirectional"))
      (node (ref "R11") (pin "1") (pinfunction "1_1") (pintype "passive"))
      (node (ref "SJ1") (pin "2") (pinfunction "2_2") (pintype "passive"))
      (node (ref "U$3") (pin "13") (pinfunction "#MCLR_13") (pintype "bidirectional"))
    )
    (net (code "55") (name "/NCS1") (class "Default")
      (node (ref "CN1") (pin "19") (pinfunction "CS#_19") (pintype "bidirectional"))
      (node (ref "U$3") (pin "71") (pinfunction "EMDC/AEMDC/IC4/PMCS1/PMA14/RD11_71") (pintype "bidirectional"))
    )
    (net (code "56") (name "/NRD") (class "Default")
      (node (ref "CN1") (pin "15") (pinfunction "E/RD#_15") (pintype "bidirectional"))
      (node (ref "U$3") (pin "82") (pinfunction "PMRD/CN14/RD5_82") (pintype "bidirectional"))
    )
    (net (code "57") (name "/NWR") (class "Default")
      (node (ref "CN1") (pin "16") (pinfunction "R/W#_16") (pintype "bidirectional"))
      (node (ref "U$3") (pin "81") (pinfunction "OC5/PMWR/CN13/RD4_81") (pintype "bidirectional"))
    )
    (net (code "58") (name "/OSC1") (class "Default")
      (node (ref "C5") (pin "1") (pinfunction "1_1") (pintype "passive"))
      (node (ref "U$3") (pin "63") (pinfunction "OSC1/CLKI/RC12_63") (pintype "bidirectional"))
      (node (ref "X1") (pin "1") (pinfunction "P$1_1") (pintype "bidirectional"))
    )
    (net (code "59") (name "/OSC2") (class "Default")
      (node (ref "C6") (pin "1") (pinfunction "1_1") (pintype "passive"))
      (node (ref "U$3") (pin "64") (pinfunction "OSC2/CLKO/RC15_64") (pintype "bidirectional"))
      (node (ref "X1") (pin "2") (pinfunction "P$2_2") (pintype "bidirectional"))
    )
    (net (code "60") (name "/PGEC2") (class "Default")
      (node (ref "CN2") (pin "5") (pinfunction "5_5") (pintype "bidirectional"))
      (node (ref "U$3") (pin "26") (pinfunction "PGEC2/AN6/OCFA/RB6_26") (pintype "bidirectional"))
    )
    (net (code "61") (name "/PGED2") (class "Default")
      (node (ref "CN2") (pin "4") (pinfunction "4_4") (pintype "bidirectional"))
      (node (ref "U$3") (pin "27") (pinfunction "PGED2/AN7/RB7_27") (pintype "bidirectional"))
    )
    (net (code "62") (name "/RG0{slash}RAD_SIG2") (class "Default")
      (node (ref "CN3") (pin "3") (pinfunction "3_3") (pintype "bidirectional"))
      (node (ref "U$3") (pin "90") (pinfunction "PMD8/RG0_90") (pintype "bidirectional"))
    )
    (net (code "63") (name "/RG1{slash}RAD_NS") (class "Default")
      (node (ref "CN3") (pin "4") (pinfunction "4_4") (pintype "bidirectional"))
      (node (ref "U$3") (pin "89") (pinfunction "ETXERR/PMD9/RG1_89") (pintype "bidirectional"))
    )
    (net (code "64") (name "/SCL1") (class "Default")
      (node (ref "CN4") (pin "10") (pinfunction "10_10") (pintype "bidirectional"))
      (node (ref "CN6") (pin "11") (pinfunction "11_11") (pintype "bidirectional"))
      (node (ref "CN7") (pin "11") (pinfunction "11_11") (pintype "bidirectional"))
      (node (ref "CN8") (pin "11") (pinfunction "11_11") (pintype "bidirectional"))
      (node (ref "CN9") (pin "11") (pinfunction "11_11") (pintype "bidirectional"))
      (node (ref "R17") (pin "1") (pinfunction "1_1") (pintype "passive"))
      (node (ref "U$3") (pin "66") (pinfunction "AETXCLK/SCL1/INT3/RA14_66") (pintype "bidirectional"))
    )
    (net (code "65") (name "/SDA1") (class "Default")
      (node (ref "CN4") (pin "8") (pinfunction "8_8") (pintype "bidirectional"))
      (node (ref "CN6") (pin "9") (pinfunction "9_9") (pintype "bidirectional"))
      (node (ref "CN7") (pin "9") (pinfunction "9_9") (pintype "bidirectional"))
      (node (ref "CN8") (pin "9") (pinfunction "9_9") (pintype "bidirectional"))
      (node (ref "CN9") (pin "9") (pinfunction "9_9") (pintype "bidirectional"))
      (node (ref "R16") (pin "1") (pinfunction "1_1") (pintype "passive"))
      (node (ref "U$3") (pin "67") (pinfunction "AETXEN/SDA1/INT4/RA15_67") (pintype "bidirectional"))
    )
    (net (code "66") (name "/SPI2_CLK") (class "Default")
      (node (ref "CN6") (pin "3") (pinfunction "3_3") (pintype "bidirectional"))
      (node (ref "CN7") (pin "3") (pinfunction "3_3") (pintype "bidirectional"))
      (node (ref "CN8") (pin "3") (pinfunction "3_3") (pintype "bidirectional"))
      (node (ref "CN9") (pin "3") (pinfunction "3_3") (pintype "bidirectional"))
      (node (ref "U$3") (pin "70") (pinfunction "SCK1/IC3/PMCS2/PMA15/RD10_70") (pintype "bidirectional"))
    )
    (net (code "67") (name "/SPI2_MISO") (class "Default")
      (node (ref "CN6") (pin "7") (pinfunction "7_7") (pintype "bidirectional"))
      (node (ref "CN7") (pin "7") (pinfunction "7_7") (pintype "bidirectional"))
      (node (ref "CN8") (pin "7") (pinfunction "7_7") (pintype "bidirectional"))
      (node (ref "CN9") (pin "7") (pinfunction "7_7") (pintype "bidirectional"))
      (node (ref "U$3") (pin "9") (pinfunction "T5CK/SDI1/RC4_9") (pintype "bidirectional"))
    )
    (net (code "68") (name "/SPI2_MOSI") (class "Default")
      (node (ref "CN6") (pin "5") (pinfunction "5_5") (pintype "bidirectional"))
      (node (ref "CN7") (pin "5") (pinfunction "5_5") (pintype "bidirectional"))
      (node (ref "CN8") (pin "5") (pinfunction "5_5") (pintype "bidirectional"))
      (node (ref "CN9") (pin "5") (pinfunction "5_5") (pintype "bidirectional"))
      (node (ref "U$3") (pin "72") (pinfunction "SDO1/OC1/INT0/RD0_72") (pintype "bidirectional"))
    )
    (net (code "69") (name "/SPI_CLK") (class "Default")
      (node (ref "U$12") (pin "17") (pinfunction "SPI_CLK_17") (pintype "bidirectional"))
      (node (ref "U$3") (pin "10") (pinfunction "ECOL/SCK2A/U2BTX/#U2ARTS/PMA5/CN8/RG6_10") (pintype "bidirectional"))
      (node (ref "U$7") (pin "5") (pinfunction "CLK_5") (pintype "bidirectional"))
    )
    (net (code "70") (name "/SPI_MISO") (class "Default")
      (node (ref "U$15") (pin "4") (pinfunction "OUT_4") (pintype "bidirectional"))
      (node (ref "U$3") (pin "11") (pinfunction "ECRS/SDA2A/SDI2A/U2ARX/PMA4/CN9/RG7_11") (pintype "bidirectional"))
      (node (ref "U$7") (pin "7") (pinfunction "DAT0_7") (pintype "bidirectional"))
    )
    (net (code "71") (name "/SPI_MOSI") (class "Default")
      (node (ref "U$12") (pin "15") (pinfunction "SPI_MOSI_15") (pintype "bidirectional"))
      (node (ref "U$3") (pin "12") (pinfunction "ETHERNET/SCL2A/SDO2A/U2ATX/PMA3/CN10/RG8_12") (pintype "bidirectional"))
      (node (ref "U$7") (pin "3") (pinfunction "CMD_3") (pintype "bidirectional"))
    )
    (net (code "72") (name "/U1ARX") (class "Default")
      (node (ref "R4") (pin "2") (pinfunction "2_2") (pintype "passive"))
      (node (ref "U$3") (pin "52") (pinfunction "SDA1A/SDI1A/U1ARX/RF2_52") (pintype "bidirectional"))
    )
    (net (code "73") (name "/U1ATX") (class "Default")
      (node (ref "R5") (pin "2") (pinfunction "2_2") (pintype "passive"))
      (node (ref "U$3") (pin "53") (pinfunction "SCL1A/SDO1A/U1ATX/RF8_53") (pintype "bidirectional"))
    )
    (net (code "74") (name "/U1BRX") (class "Default")
      (node (ref "CN9") (pin "15") (pinfunction "15_15") (pintype "bidirectional"))
      (node (ref "U$3") (pin "47") (pinfunction "AETXD0/#SS1A/U1BRX/#U1ACTS/CN20/RD14_47") (pintype "bidirectional"))
    )
    (net (code "75") (name "/U1BTX") (class "Default")
      (node (ref "CN9") (pin "13") (pinfunction "13_13") (pintype "bidirectional"))
      (node (ref "U$3") (pin "48") (pinfunction "AETXD1/SCK1A/U1BTX/#U1ARTS/CN21/RD15_48") (pintype "bidirectional"))
    )
    (net (code "76") (name "/U3ARX") (class "Default")
      (node (ref "CN8") (pin "15") (pinfunction "15_15") (pintype "bidirectional"))
      (node (ref "U$3") (pin "49") (pinfunction "SDA3A/SDI3A/U3ARX/PMA9/CN17/RF4_49") (pintype "bidirectional"))
    )
    (net (code "77") (name "/U3ATX") (class "Default")
      (node (ref "CN8") (pin "13") (pinfunction "13_13") (pintype "bidirectional"))
      (node (ref "U$3") (pin "50") (pinfunction "SCL3A/SDO3A/U3ATX/PMA8/CN18/RF5_50") (pintype "bidirectional"))
    )
    (net (code "78") (name "/U3BRX") (class "Default")
      (node (ref "CN6") (pin "15") (pinfunction "15_15") (pintype "bidirectional"))
      (node (ref "U$3") (pin "40") (pinfunction "#SS3A/U3BRX/#U3ACTS/RF12_40") (pintype "bidirectional"))
    )
    (net (code "79") (name "/U3BTX") (class "Default")
      (node (ref "CN6") (pin "13") (pinfunction "13_13") (pintype "bidirectional"))
      (node (ref "U$3") (pin "39") (pinfunction "SCK3A/U3BTX/#U3ARTS/RF13_39") (pintype "bidirectional"))
    )
    (net (code "80") (name "/VBAT") (class "Default")
      (node (ref "C27") (pin "1") (pinfunction "1_1") (pintype "passive"))
      (node (ref "CN5") (pin "2") (pinfunction "1_2") (pintype "passive"))
      (node (ref "D3") (pin "ANODE") (pinfunction "ANODE_ANODE") (pintype "bidirectional"))
      (node (ref "U1") (pin "3") (pinfunction "VBAT_3") (pintype "power_in"))
    )
    (net (code "81") (name "/VIN") (class "Default")
      (node (ref "C30") (pin "2") (pinfunction "2_2") (pintype "passive"))
      (node (ref "C35") (pin "1") (pinfunction "1_1") (pintype "passive"))
      (node (ref "CN4") (pin "3") (pinfunction "3_3") (pintype "bidirectional"))
      (node (ref "D2") (pin "CATHODE") (pinfunction "CATHODE_CATHODE") (pintype "bidirectional"))
      (node (ref "D3") (pin "CATHODE") (pinfunction "CATHODE_CATHODE") (pintype "bidirectional"))
      (node (ref "U$12") (pin "19") (pinfunction "VBAT_IN_19") (pintype "bidirectional"))
      (node (ref "U$2") (pin "5") (pinfunction "VIN_5") (pintype "bidirectional"))
      (node (ref "U$2") (pin "7") (pinfunction "PS/SYNC_7") (pintype "bidirectional"))
      (node (ref "U$2") (pin "8") (pinfunction "VINA_8") (pintype "bidirectional"))
      (node (ref "U$5") (pin "P") (pinfunction "P_P") (pintype "passive"))
    )
    (net (code "82") (name "3.3V") (class "Default")
      (node (ref "C1") (pin "1") (pinfunction "1_1") (pintype "passive"))
      (node (ref "C10") (pin "2") (pinfunction "2_2") (pintype "passive"))
      (node (ref "C11") (pin "2") (pinfunction "2_2") (pintype "passive"))
      (node (ref "C12") (pin "2") (pinfunction "2_2") (pintype "passive"))
      (node (ref "C13") (pin "1") (pinfunction "1_1") (pintype "passive"))
      (node (ref "C17") (pin "1") (pinfunction "1_1") (pintype "passive"))
      (node (ref "C18") (pin "2") (pinfunction "2_2") (pintype "passive"))
      (node (ref "C20") (pin "1") (pinfunction "1_1") (pintype "passive"))
      (node (ref "C21") (pin "1") (pinfunction "1_1") (pintype "passive"))
      (node (ref "C22") (pin "1") (pinfunction "1_1") (pintype "passive"))
      (node (ref "C28") (pin "1") (pinfunction "1_1") (pintype "passive"))
      (node (ref "C8") (pin "2") (pinfunction "2_2") (pintype "passive"))
      (node (ref "C9") (pin "1") (pinfunction "1_1") (pintype "passive"))
      (node (ref "CN1") (pin "17") (pinfunction "BS0_17") (pintype "bidirectional"))
      (node (ref "CN1") (pin "18") (pinfunction "BS1_18") (pintype "bidirectional"))
      (node (ref "CN1") (pin "27") (pinfunction "VCI_27") (pintype "bidirectional"))
      (node (ref "CN1") (pin "4") (pinfunction "VDDIO_4") (pintype "bidirectional"))
      (node (ref "CN2") (pin "2") (pinfunction "2_2") (pintype "bidirectional"))
      (node (ref "CN3") (pin "1") (pinfunction "1_1") (pintype "bidirectional"))
      (node (ref "CN4") (pin "5") (pinfunction "5_5") (pintype "bidirectional"))
      (node (ref "CN6") (pin "2") (pinfunction "2_2") (pintype "bidirectional"))
      (node (ref "CN7") (pin "2") (pinfunction "2_2") (pintype "bidirectional"))
      (node (ref "CN8") (pin "2") (pinfunction "2_2") (pintype "bidirectional"))
      (node (ref "CN9") (pin "2") (pinfunction "2_2") (pintype "bidirectional"))
      (node (ref "L1") (pin "2") (pinfunction "2_2") (pintype "bidirectional"))
      (node (ref "R10") (pin "1") (pinfunction "1_1") (pintype "passive"))
      (node (ref "R11") (pin "2") (pinfunction "2_2") (pintype "passive"))
      (node (ref "R16") (pin "2") (pinfunction "2_2") (pintype "passive"))
      (node (ref "R17") (pin "2") (pinfunction "2_2") (pintype "passive"))
      (node (ref "U$12") (pin "23") (pinfunction "VIO_23") (pintype "bidirectional"))
      (node (ref "U$15") (pin "5") (pinfunction "VCC_5") (pintype "bidirectional"))
      (node (ref "U$2") (pin "1") (pinfunction "VOUT_1") (pintype "bidirectional"))
      (node (ref "U$2") (pin "10") (pinfunction "FB_10") (pintype "bidirectional"))
      (node (ref "U$24") (pin "5") (pinfunction "VIN_5") (pintype "bidirectional"))
      (node (ref "U$3") (pin "16") (pinfunction "VDD2_16") (pintype "bidirectional"))
      (node (ref "U$3") (pin "2") (pinfunction "VDD1_2") (pintype "bidirectional"))
      (node (ref "U$3") (pin "30") (pinfunction "AVDD_30") (pintype "bidirectional"))
      (node (ref "U$3") (pin "37") (pinfunction "VDD3_37") (pintype "bidirectional"))
      (node (ref "U$3") (pin "46") (pinfunction "VDD4_46") (pintype "bidirectional"))
      (node (ref "U$3") (pin "55") (pinfunction "VUSB_55") (pintype "bidirectional"))
      (node (ref "U$3") (pin "62") (pinfunction "VDD5_62") (pintype "bidirectional"))
      (node (ref "U$3") (pin "86") (pinfunction "VDD6_86") (pintype "bidirectional"))
      (node (ref "U$7") (pin "4") (pinfunction "VDD_4") (pintype "bidirectional"))
      (node (ref "U$9") (pin "1") (pinfunction "VCCIO_1") (pintype "power_in"))
    )
    (net (code "83") (name "5V") (class "Default")
      (node (ref "C48") (pin "1") (pinfunction "1_1") (pintype "passive"))
      (node (ref "D2") (pin "ANODE") (pinfunction "ANODE_ANODE") (pintype "bidirectional"))
      (node (ref "D4") (pin "ANODE") (pinfunction "ANODE_ANODE") (pintype "bidirectional"))
      (node (ref "D5") (pin "ANODE") (pinfunction "ANODE_ANODE") (pintype "bidirectional"))
      (node (ref "R13") (pin "2") (pinfunction "2_2") (pintype "passive"))
      (node (ref "R6") (pin "2") (pinfunction "2_2") (pintype "passive"))
      (node (ref "U$8") (pin "1") (pinfunction "VCC_1") (pintype "bidirectional"))
      (node (ref "U$9") (pin "19") (pinfunction "VCC_19") (pintype "power_in"))
      (node (ref "U1") (pin "4") (pinfunction "VIN_4") (pintype "power_in"))
    )
    (net (code "84") (name "GND") (class "Default")
      (node (ref "C1") (pin "2") (pinfunction "2_2") (pintype "passive"))
      (node (ref "C10") (pin "1") (pinfunction "1_1") (pintype "passive"))
      (node (ref "C11") (pin "1") (pinfunction "1_1") (pintype "passive"))
      (node (ref "C12") (pin "1") (pinfunction "1_1") (pintype "passive"))
      (node (ref "C13") (pin "2") (pinfunction "2_2") (pintype "passive"))
      (node (ref "C14") (pin "2") (pinfunction "2_2") (pintype "passive"))
      (node (ref "C15") (pin "2") (pinfunction "2_2") (pintype "passive"))
      (node (ref "C16") (pin "2") (pinfunction "2_2") (pintype "passive"))
      (node (ref "C17") (pin "2") (pinfunction "2_2") (pintype "passive"))
      (node (ref "C18") (pin "1") (pinfunction "1_1") (pintype "passive"))
      (node (ref "C19") (pin "2") (pinfunction "2_2") (pintype "passive"))
      (node (ref "C20") (pin "2") (pinfunction "2_2") (pintype "passive"))
      (node (ref "C21") (pin "2") (pinfunction "2_2") (pintype "passive"))
      (node (ref "C22") (pin "2") (pinfunction "2_2") (pintype "passive"))
      (node (ref "C27") (pin "2") (pinfunction "2_2") (pintype "passive"))
      (node (ref "C28") (pin "2") (pinfunction "2_2") (pintype "passive"))
      (node (ref "C30") (pin "1") (pinfunction "1_1") (pintype "passive"))
      (node (ref "C31") (pin "2") (pinfunction "2_2") (pintype "passive"))
      (node (ref "C35") (pin "2") (pinfunction "2_2") (pintype "passive"))
      (node (ref "C4") (pin "2") (pinfunction "2_2") (pintype "passive"))
      (node (ref "C48") (pin "2") (pinfunction "2_2") (pintype "passive"))
      (node (ref "C5") (pin "2") (pinfunction "2_2") (pintype "passive"))
      (node (ref "C6") (pin "2") (pinfunction "2_2") (pintype "passive"))
      (node (ref "C7") (pin "C") (pinfunction "-_C") (pintype "passive"))
      (node (ref "C8") (pin "1") (pinfunction "1_1") (pintype "passive"))
      (node (ref "C9") (pin "2") (pinfunction "2_2") (pintype "passive"))
      (node (ref "CN1") (pin "1") (pinfunction "GND1_1") (pintype "bidirectional"))
      (node (ref "CN1") (pin "28") (pinfunction "VSS_28") (pintype "bidirectional"))
      (node (ref "CN1") (pin "30") (pinfunction "GND2_30") (pintype "bidirectional"))
      (node (ref "CN1") (pin "PAD1") (pinfunction "PAD1_PAD1") (pintype "bidirectional"))
      (node (ref "CN1") (pin "PAD2") (pinfunction "PAD2_PAD2") (pintype "bidirectional"))
      (node (ref "CN2") (pin "3") (pinfunction "3_3") (pintype "bidirectional"))
      (node (ref "CN3") (pin "5") (pinfunction "5_5") (pintype "bidirectional"))
      (node (ref "CN4") (pin "1") (pinfunction "1_1") (pintype "bidirectional"))
      (node (ref "CN4") (pin "9") (pinfunction "9_9") (pintype "bidirectional"))
      (node (ref "CN4") (pin "PAD1") (pinfunction "PAD1_PAD1") (pintype "bidirectional"))
      (node (ref "CN4") (pin "PAD2") (pinfunction "PAD2_PAD2") (pintype "bidirectional"))
      (node (ref "CN5") (pin "1") (pinfunction "2_1") (pintype "passive"))
      (node (ref "CN6") (pin "1") (pinfunction "1_1") (pintype "bidirectional"))
      (node (ref "CN7") (pin "1") (pinfunction "1_1") (pintype "bidirectional"))
      (node (ref "CN8") (pin "1") (pinfunction "1_1") (pintype "bidirectional"))
      (node (ref "CN9") (pin "1") (pinfunction "1_1") (pintype "bidirectional"))
      (node (ref "D10") (pin "1") (pinfunction "CATHODE_1") (pintype "bidirectional"))
      (node (ref "R12") (pin "1") (pinfunction "1_1") (pintype "passive"))
      (node (ref "R14") (pin "1") (pinfunction "1_1") (pintype "passive"))
      (node (ref "R15") (pin "1") (pinfunction "1_1") (pintype "passive"))
      (node (ref "R19") (pin "1") (pinfunction "1_1") (pintype "passive"))
      (node (ref "R36") (pin "1") (pinfunction "1_1") (pintype "passive"))
      (node (ref "R7") (pin "1") (pinfunction "1_1") (pintype "passive"))
      (node (ref "R9") (pin "1") (pinfunction "1_1") (pintype "passive"))
      (node (ref "U$12") (pin "1") (pinfunction "GND_1") (pintype "bidirectional"))
      (node (ref "U$12") (pin "10") (pinfunction "GND_10") (pintype "bidirectional"))
      (node (ref "U$12") (pin "11") (pinfunction "GND_11") (pintype "bidirectional"))
      (node (ref "U$12") (pin "16") (pinfunction "GND_16") (pintype "bidirectional"))
      (node (ref "U$12") (pin "18") (pinfunction "GND_18") (pintype "bidirectional"))
      (node (ref "U$12") (pin "20") (pinfunction "GND_20") (pintype "bidirectional"))
      (node (ref "U$12") (pin "21") (pinfunction "EXT_32K_21") (pintype "bidirectional"))
      (node (ref "U$12") (pin "22") (pinfunction "GND_22") (pintype "bidirectional"))
      (node (ref "U$12") (pin "25") (pinfunction "GND_25") (pintype "bidirectional"))
      (node (ref "U$12") (pin "31") (pinfunction "GND_31") (pintype "bidirectional"))
      (node (ref "U$12") (pin "32") (pinfunction "GND_32") (pintype "bidirectional"))
      (node (ref "U$12") (pin "33") (pinfunction "GND_33") (pintype "bidirectional"))
      (node (ref "U$12") (pin "34") (pinfunction "GND_34") (pintype "bidirectional"))
      (node (ref "U$12") (pin "36") (pinfunction "GND_36") (pintype "bidirectional"))
      (node (ref "U$12") (pin "37") (pinfunction "GND_37") (pintype "bidirectional"))
      (node (ref "U$12") (pin "38") (pinfunction "GND_38") (pintype "bidirectional"))
      (node (ref "U$12") (pin "39") (pinfunction "GND_39") (pintype "bidirectional"))
      (node (ref "U$12") (pin "40") (pinfunction "GND_40") (pintype "bidirectional"))
      (node (ref "U$12") (pin "41") (pinfunction "GND_41") (pintype "bidirectional"))
      (node (ref "U$12") (pin "42") (pinfunction "GND_42") (pintype "bidirectional"))
      (node (ref "U$12") (pin "43") (pinfunction "GND_43") (pintype "bidirectional"))
      (node (ref "U$12") (pin "44") (pinfunction "GND_44") (pintype "bidirectional"))
      (node (ref "U$12") (pin "45") (pinfunction "GND_45") (pintype "bidirectional"))
      (node (ref "U$12") (pin "46") (pinfunction "GND_46") (pintype "bidirectional"))
      (node (ref "U$12") (pin "9") (pinfunction "GND_9") (pintype "bidirectional"))
      (node (ref "U$15") (pin "3") (pinfunction "GND_3") (pintype "bidirectional"))
      (node (ref "U$2") (pin "3") (pinfunction "PGND_3") (pintype "bidirectional"))
      (node (ref "U$2") (pin "9") (pinfunction "GND_9") (pintype "bidirectional"))
      (node (ref "U$2") (pin "TH1") (pinfunction "THERM1_TH1") (pintype "bidirectional"))
      (node (ref "U$2") (pin "TH2") (pinfunction "THERM2_TH2") (pintype "bidirectional"))
      (node (ref "U$2") (pin "TH3") (pinfunction "THERM3_TH3") (pintype "bidirectional"))
      (node (ref "U$2") (pin "TH4") (pinfunction "THERM4_TH4") (pintype "bidirectional"))
      (node (ref "U$24") (pin "2") (pinfunction "GND_2") (pintype "bidirectional"))
      (node (ref "U$3") (pin "15") (pinfunction "VSS1_15") (pintype "bidirectional"))
      (node (ref "U$3") (pin "31") (pinfunction "AVSS_31") (pintype "bidirectional"))
      (node (ref "U$3") (pin "36") (pinfunction "VSS2_36") (pintype "bidirectional"))
      (node (ref "U$3") (pin "45") (pinfunction "VSS3_45") (pintype "bidirectional"))
      (node (ref "U$3") (pin "65") (pinfunction "VSS4_65") (pintype "bidirectional"))
      (node (ref "U$3") (pin "75") (pinfunction "VSS5_75") (pintype "bidirectional"))
      (node (ref "U$7") (pin "6") (pinfunction "GND_6") (pintype "bidirectional"))
      (node (ref "U$7") (pin "9") (pinfunction "CDET1_9") (pintype "bidirectional"))
      (node (ref "U$8") (pin "5") (pinfunction "GND_5") (pintype "bidirectional"))
      (node (ref "U$8") (pin "S1") (pinfunction "SH1_S1") (pintype "bidirectional"))
      (node (ref "U$8") (pin "S2") (pinfunction "SH2_S2") (pintype "bidirectional"))
      (node (ref "U$8") (pin "S3") (pinfunction "SH3_S3") (pintype "bidirectional"))
      (node (ref "U$8") (pin "S4") (pinfunction "SH4_S4") (pintype "bidirectional"))
      (node (ref "U$9") (pin "17") (pinfunction "GND_17") (pintype "power_in"))
      (node (ref "U$9") (pin "20") (pinfunction "GND_20") (pintype "power_in"))
      (node (ref "U$9") (pin "24") (pinfunction "AGND_24") (pintype "power_in"))
      (node (ref "U$9") (pin "26") (pinfunction "TEST_26") (pintype "input"))
      (node (ref "U$9") (pin "4") (pinfunction "GND_4") (pintype "power_in"))
      (node (ref "U1") (pin "2") (pinfunction "VSS_2") (pintype "power_in"))
    )
    (net (code "85") (name "Net-(C3-Pad2)") (class "Default")
      (node (ref "C3") (pin "2") (pinfunction "2_2") (pintype "passive"))
      (node (ref "R3") (pin "2") (pinfunction "2_2") (pintype "passive"))
      (node (ref "SJ1") (pin "1") (pinfunction "1_1") (pintype "passive"))
    )
    (net (code "86") (name "Net-(C7-+)") (class "Default")
      (node (ref "C7") (pin "A") (pinfunction "+_A") (pintype "passive"))
      (node (ref "U$3") (pin "85") (pinfunction "VCAP/VDDCORE_85") (pintype "bidirectional"))
    )
    (net (code "87") (name "Net-(C31-Pad1)") (class "Default")
      (node (ref "C31") (pin "1") (pinfunction "1_1") (pintype "passive"))
      (node (ref "L6") (pin "2") (pinfunction "2_2") (pintype "passive"))
      (node (ref "U$6") (pin "1") (pinfunction "1_1") (pintype "bidirectional"))
    )
    (net (code "88") (name "Net-(CN1-IREF)") (class "Default")
      (node (ref "CN1") (pin "22") (pinfunction "IREF_22") (pintype "bidirectional"))
      (node (ref "R15") (pin "2") (pinfunction "2_2") (pintype "passive"))
    )
    (net (code "89") (name "Net-(CN1-VCOMH)") (class "Default")
      (node (ref "C15") (pin "1") (pinfunction "1_1") (pintype "passive"))
      (node (ref "CN1") (pin "3") (pinfunction "VCOMH_3") (pintype "bidirectional"))
    )
    (net (code "90") (name "Net-(CN1-VDD)") (class "Default")
      (node (ref "C16") (pin "1") (pinfunction "1_1") (pintype "passive"))
      (node (ref "CN1") (pin "26") (pinfunction "VDD_26") (pintype "bidirectional"))
    )
    (net (code "91") (name "Net-(CN1-VSL)") (class "Default")
      (node (ref "CN1") (pin "5") (pinfunction "VSL_5") (pintype "bidirectional"))
      (node (ref "R18") (pin "2") (pinfunction "2_2") (pintype "passive"))
    )
    (net (code "92") (name "Net-(D4-PadCATHODE)") (class "Default")
      (node (ref "D4") (pin "CATHODE") (pinfunction "CATHODE_CATHODE") (pintype "bidirectional"))
      (node (ref "R1") (pin "2") (pinfunction "2_2") (pintype "passive"))
    )
    (net (code "93") (name "Net-(D5-PadCATHODE)") (class "Default")
      (node (ref "D5") (pin "CATHODE") (pinfunction "CATHODE_CATHODE") (pintype "bidirectional"))
      (node (ref "R2") (pin "2") (pinfunction "2_2") (pintype "passive"))
    )
    (net (code "94") (name "Net-(D8-ANODE)") (class "Default")
      (node (ref "D8") (pin "2") (pinfunction "ANODE_2") (pintype "bidirectional"))
      (node (ref "L1") (pin "1") (pinfunction "1_1") (pintype "bidirectional"))
      (node (ref "U$24") (pin "1") (pinfunction "SW_1") (pintype "bidirectional"))
    )
    (net (code "95") (name "Net-(D9-ANODE)") (class "Default")
      (node (ref "D9") (pin "2") (pinfunction "ANODE_2") (pintype "bidirectional"))
      (node (ref "R18") (pin "1") (pinfunction "1_1") (pintype "passive"))
    )
    (net (code "96") (name "Net-(D10-ANODE)") (class "Default")
      (node (ref "D10") (pin "2") (pinfunction "ANODE_2") (pintype "bidirectional"))
      (node (ref "D9") (pin "1") (pinfunction "CATHODE_1") (pintype "bidirectional"))
    )
    (net (code "97") (name "Net-(U$2-L1)") (class "Default")
      (node (ref "L3") (pin "1") (pinfunction "1_1") (pintype "bidirectional"))
      (node (ref "U$2") (pin "4") (pinfunction "L1_4") (pintype "bidirectional"))
    )
    (net (code "98") (name "Net-(U$2-L2)") (class "Default")
      (node (ref "L3") (pin "2") (pinfunction "2_2") (pintype "bidirectional"))
      (node (ref "U$2") (pin "2") (pinfunction "L2_2") (pintype "bidirectional"))
    )
    (net (code "99") (name "Net-(U$8-D+)") (class "Default")
      (node (ref "U$8") (pin "3") (pinfunction "D+_3") (pintype "bidirectional"))
      (node (ref "U$9") (pin "14") (pinfunction "USBDP_14") (pintype "bidirectional"))
    )
    (net (code "100") (name "Net-(U$8-D-)") (class "Default")
      (node (ref "U$8") (pin "2") (pinfunction "D-_2") (pintype "bidirectional"))
      (node (ref "U$9") (pin "15") (pinfunction "USBDM_15") (pintype "bidirectional"))
    )
    (net (code "101") (name "Net-(U$9-DTR)") (class "Default")
      (node (ref "C3") (pin "1") (pinfunction "1_1") (pintype "passive"))
      (node (ref "U$9") (pin "31") (pinfunction "DTR_31") (pintype "output"))
    )
    (net (code "102") (name "Net-(U$9-RESET)") (class "Default")
      (node (ref "C4") (pin "1") (pinfunction "1_1") (pintype "passive"))
      (node (ref "R6") (pin "1") (pinfunction "1_1") (pintype "passive"))
      (node (ref "R7") (pin "2") (pinfunction "2_2") (pintype "passive"))
      (node (ref "U$9") (pin "18") (pinfunction "RESET_18") (pintype "input"))
    )
    (net (code "103") (name "Net-(U$9-RTS)") (class "Default")
      (node (ref "R3") (pin "1") (pinfunction "1_1") (pintype "passive"))
      (node (ref "U$9") (pin "32") (pinfunction "RTS_32") (pintype "output"))
    )
    (net (code "104") (name "Net-(U$9-RXD)") (class "Default")
      (node (ref "R5") (pin "1") (pinfunction "1_1") (pintype "passive"))
      (node (ref "U$9") (pin "2") (pinfunction "RXD_2") (pintype "input"))
    )
    (net (code "105") (name "Net-(U$9-RXLED)") (class "Default")
      (node (ref "R2") (pin "1") (pinfunction "1_1") (pintype "passive"))
      (node (ref "U$9") (pin "21") (pinfunction "RXLED_21") (pintype "input"))
    )
    (net (code "106") (name "Net-(U$9-TXD)") (class "Default")
      (node (ref "R4") (pin "1") (pinfunction "1_1") (pintype "passive"))
      (node (ref "U$9") (pin "30") (pinfunction "TXD_30") (pintype "output"))
    )
    (net (code "107") (name "Net-(U$9-TXLED)") (class "Default")
      (node (ref "R1") (pin "1") (pinfunction "1_1") (pintype "passive"))
      (node (ref "U$9") (pin "22") (pinfunction "TXLED_22") (pintype "input"))
    )
    (net (code "108") (name "Net-(U$12-RF_ANT)") (class "Default")
      (node (ref "L6") (pin "1") (pinfunction "1_1") (pintype "passive"))
      (node (ref "U$12") (pin "35") (pinfunction "RF_ANT_35") (pintype "bidirectional"))
    )
    (net (code "109") (name "Net-(U$12-SCL_CC3000)") (class "Default")
      (node (ref "U$12") (pin "29") (pinfunction "SCL_EEPROM_29") (pintype "bidirectional"))
      (node (ref "U$12") (pin "30") (pinfunction "SCL_CC3000_30") (pintype "bidirectional"))
    )
    (net (code "110") (name "Net-(U$12-SDA_CC3000)") (class "Default")
      (node (ref "U$12") (pin "27") (pinfunction "SDA_EEPROM_27") (pintype "bidirectional"))
      (node (ref "U$12") (pin "28") (pinfunction "SDA_CC3000_28") (pintype "bidirectional"))
    )
    (net (code "111") (name "Net-(U$12-WL_EN1)") (class "Default")
      (node (ref "U$12") (pin "5") (pinfunction "WL_EN2_5") (pintype "bidirectional"))
      (node (ref "U$12") (pin "7") (pinfunction "WL_EN1_7") (pintype "bidirectional"))
    )
    (net (code "112") (name "Net-(U$24-FB)") (class "Default")
      (node (ref "C2") (pin "2") (pinfunction "2_2") (pintype "passive"))
      (node (ref "R8") (pin "1") (pinfunction "1_1") (pintype "passive"))
      (node (ref "R9") (pin "2") (pinfunction "2_2") (pintype "passive"))
      (node (ref "U$24") (pin "3") (pinfunction "FB_3") (pintype "bidirectional"))
    )
    (net (code "113") (name "Net-(U1-PROG)") (class "Default")
      (node (ref "R12") (pin "2") (pinfunction "2_2") (pintype "passive"))
      (node (ref "U1") (pin "5") (pinfunction "PROG_5") (pintype "input"))
    )
    (net (code "114") (name "Net-(U1-STAT)") (class "Default")
      (node (ref "D1") (pin "CATHODE") (pinfunction "CATHODE_CATHODE") (pintype "bidirectional"))
      (node (ref "U1") (pin "1") (pinfunction "STAT_1") (pintype "output"))
    )
    (net (code "115") (name "unconnected-(CN1-GPIO0-Pad24)") (class "Default")
      (node (ref "CN1") (pin "24") (pinfunction "GPIO0_24") (pintype "bidirectional"))
    )
    (net (code "116") (name "unconnected-(CN1-GPIO1-Pad23)") (class "Default")
      (node (ref "CN1") (pin "23") (pinfunction "GPIO1_23") (pintype "bidirectional"))
    )
    (net (code "117") (name "unconnected-(CN4-Pad7)") (class "Default")
      (node (ref "CN4") (pin "7") (pinfunction "7_7") (pintype "bidirectional"))
    )
    (net (code "118") (name "unconnected-(CN7-Pad13)") (class "Default")
      (node (ref "CN7") (pin "13") (pinfunction "13_13") (pintype "bidirectional"))
    )
    (net (code "119") (name "unconnected-(CN7-Pad15)") (class "Default")
      (node (ref "CN7") (pin "15") (pinfunction "15_15") (pintype "bidirectional"))
    )
    (net (code "120") (name "unconnected-(U$3-#SS1{slash}IC2{slash}RD9-Pad69)") (class "Default")
      (node (ref "U$3") (pin "69") (pinfunction "#SS1/IC2/RD9_69") (pintype "bidirectional"))
    )
    (net (code "121") (name "unconnected-(U$3-ETXCLK{slash}PMD15{slash}CN16{slash}RD7-Pad84)") (class "Default")
      (node (ref "U$3") (pin "84") (pinfunction "ETXCLK/PMD15/CN16/RD7_84") (pintype "bidirectional"))
    )
    (net (code "122") (name "unconnected-(U$3-ETXD3{slash}PMD13{slash}CN19{slash}RD13-Pad80)") (class "Default")
      (node (ref "U$3") (pin "80") (pinfunction "ETXD3/PMD13/CN19/RD13_80") (pintype "bidirectional"))
    )
    (net (code "123") (name "unconnected-(U$3-SCL2{slash}RA2-Pad58)") (class "Default")
      (node (ref "U$3") (pin "58") (pinfunction "SCL2/RA2_58") (pintype "bidirectional"))
    )
    (net (code "124") (name "unconnected-(U$3-SDA2{slash}RA3-Pad59)") (class "Default")
      (node (ref "U$3") (pin "59") (pinfunction "SDA2/RA3_59") (pintype "bidirectional"))
    )
    (net (code "125") (name "unconnected-(U$3-T2CK{slash}RC1-Pad6)") (class "Default")
      (node (ref "U$3") (pin "6") (pinfunction "T2CK/RC1_6") (pintype "bidirectional"))
    )
    (net (code "126") (name "unconnected-(U$3-TCK{slash}RA1-Pad38)") (class "Default")
      (node (ref "U$3") (pin "38") (pinfunction "TCK/RA1_38") (pintype "bidirectional"))
    )
    (net (code "127") (name "unconnected-(U$3-VBUS-Pad54)") (class "Default")
      (node (ref "U$3") (pin "54") (pinfunction "VBUS_54") (pintype "bidirectional"))
    )
    (net (code "128") (name "unconnected-(U$3-VREF+{slash}CVREF+{slash}AERXD3{slash}PMA6{slash}RA10-Pad29)") (class "Default")
      (node (ref "U$3") (pin "29") (pinfunction "VREF+/CVREF+/AERXD3/PMA6/RA10_29") (pintype "bidirectional"))
    )
    (net (code "129") (name "unconnected-(U$3-VREF-{slash}CVREF-{slash}AERXD2{slash}PMA7{slash}RA9-Pad28)") (class "Default")
      (node (ref "U$3") (pin "28") (pinfunction "VREF-/CVREF-/AERXD2/PMA7/RA9_28") (pintype "bidirectional"))
    )
    (net (code "130") (name "unconnected-(U$5-PadS)") (class "Default")
      (node (ref "U$5") (pin "S") (pinfunction "S_S") (pintype "passive"))
    )
    (net (code "131") (name "unconnected-(U$7-DAT1-Pad8)") (class "Default")
      (node (ref "U$7") (pin "8") (pinfunction "DAT1_8") (pintype "bidirectional"))
    )
    (net (code "132") (name "unconnected-(U$7-DAT2-Pad1)") (class "Default")
      (node (ref "U$7") (pin "1") (pinfunction "DAT2_1") (pintype "bidirectional"))
    )
    (net (code "133") (name "unconnected-(U$8-ID-Pad4)") (class "Default")
      (node (ref "U$8") (pin "4") (pinfunction "ID_4") (pintype "bidirectional"))
    )
    (net (code "134") (name "unconnected-(U$9-3V3OUT-Pad16)") (class "Default")
      (node (ref "U$9") (pin "16") (pinfunction "3V3OUT_16") (pintype "output"))
    )
    (net (code "135") (name "unconnected-(U$9-CTS-Pad8)") (class "Default")
      (node (ref "U$9") (pin "8") (pinfunction "CTS_8") (pintype "input"))
    )
    (net (code "136") (name "unconnected-(U$9-DCD-Pad7)") (class "Default")
      (node (ref "U$9") (pin "7") (pinfunction "DCD_7") (pintype "input"))
    )
    (net (code "137") (name "unconnected-(U$9-DSR-Pad6)") (class "Default")
      (node (ref "U$9") (pin "6") (pinfunction "DSR_6") (pintype "input"))
    )
    (net (code "138") (name "unconnected-(U$9-OSCI-Pad27)") (class "Default")
      (node (ref "U$9") (pin "27") (pinfunction "OSCI_27") (pintype "input"))
    )
    (net (code "139") (name "unconnected-(U$9-OSCO-Pad28)") (class "Default")
      (node (ref "U$9") (pin "28") (pinfunction "OSCO_28") (pintype "output"))
    )
    (net (code "140") (name "unconnected-(U$9-PWREN-Pad11)") (class "Default")
      (node (ref "U$9") (pin "11") (pinfunction "PWREN_11") (pintype "input"))
    )
    (net (code "141") (name "unconnected-(U$9-RI-Pad3)") (class "Default")
      (node (ref "U$9") (pin "3") (pinfunction "RI_3") (pintype "input"))
    )
    (net (code "142") (name "unconnected-(U$9-SLEEP-Pad9)") (class "Default")
      (node (ref "U$9") (pin "9") (pinfunction "SLEEP_9") (pintype "input"))
    )
    (net (code "143") (name "unconnected-(U$9-TXDEN-Pad10)") (class "Default")
      (node (ref "U$9") (pin "10") (pinfunction "TXDEN_10") (pintype "input"))
    )
    (net (code "144") (name "unconnected-(U$12-RESV1-Pad2)") (class "Default")
      (node (ref "U$12") (pin "2") (pinfunction "RESV1_2") (pintype "bidirectional"))
    )
    (net (code "145") (name "unconnected-(U$12-RESV2-Pad4)") (class "Default")
      (node (ref "U$12") (pin "4") (pinfunction "RESV2_4") (pintype "bidirectional"))
    )
    (net (code "146") (name "unconnected-(U$12-RESV3-Pad24)") (class "Default")
      (node (ref "U$12") (pin "24") (pinfunction "RESV3_24") (pintype "bidirectional"))
    )
    (net (code "147") (name "unconnected-(U$12-WL_RS232_RX-Pad8)") (class "Default")
      (node (ref "U$12") (pin "8") (pinfunction "WL_RS232_RX_8") (pintype "bidirectional"))
    )
    (net (code "148") (name "unconnected-(U$12-WL_RS232_TX-Pad6)") (class "Default")
      (node (ref "U$12") (pin "6") (pinfunction "WL_RS232_TX_6") (pintype "bidirectional"))
    )
  )
)
